# seismometer_energyboard.net
KiCad netlist of a schematic drawn in EAGLE
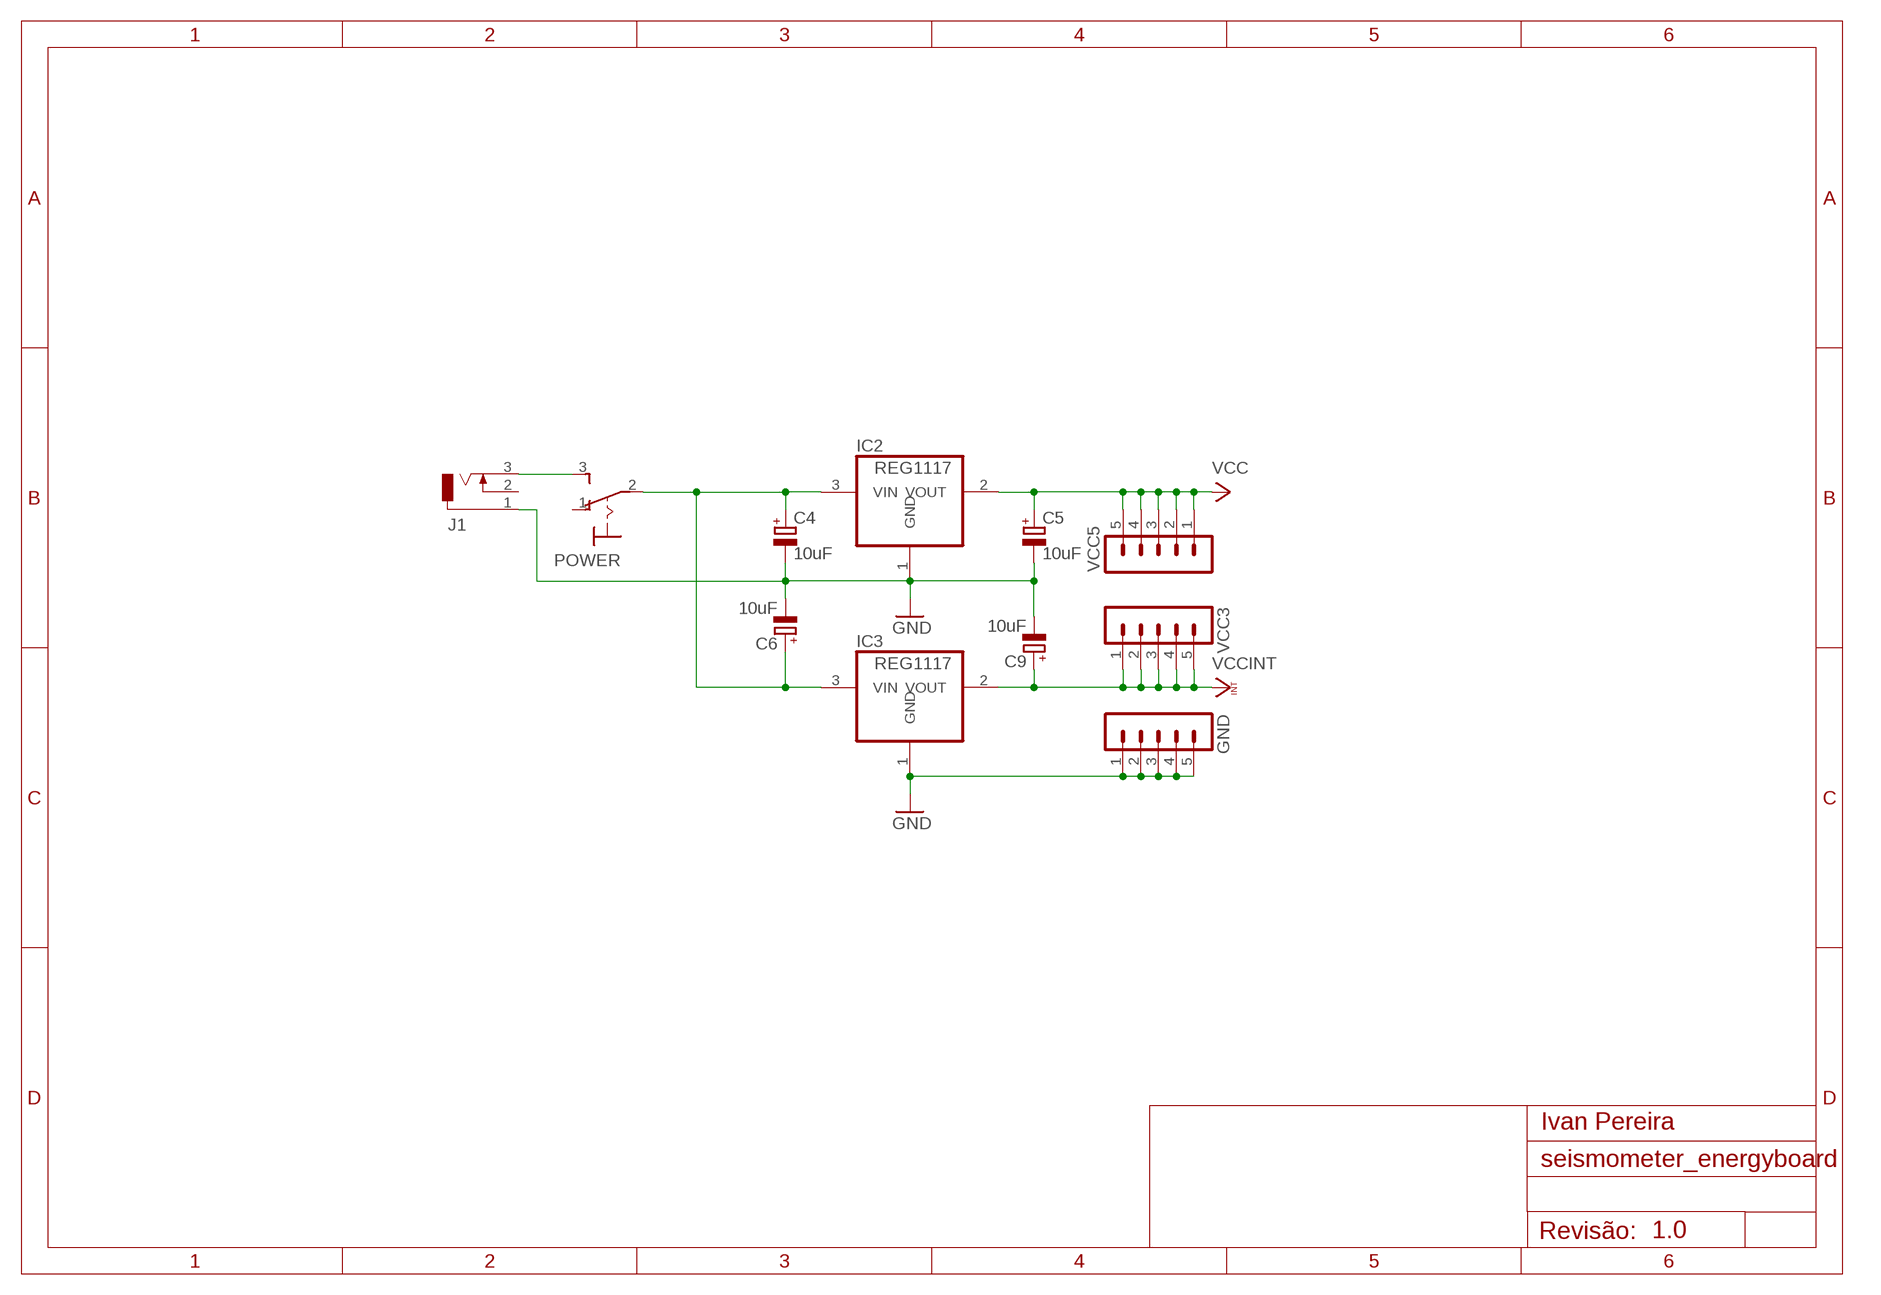
[diagram p0: schematic, sheet 1]

(export (version "E")
  (design (tool "Eeschema 10.0.6"))
  (components
    (comp (ref "C4")
      (value "10uF")
      (footprint "eagle-import:E2,5-6")
      (libsource (lib "eagle-import") (part "CPOL-EUE2.5-6"))
    )
    (comp (ref "C5")
      (value "10uF")
      (footprint "eagle-import:E2,5-6")
      (libsource (lib "eagle-import") (part "CPOL-EUE2.5-6"))
    )
    (comp (ref "C6")
      (value "10uF")
      (footprint "eagle-import:E2,5-6")
      (libsource (lib "eagle-import") (part "CPOL-EUE2.5-6"))
    )
    (comp (ref "C9")
      (value "10uF")
      (footprint "eagle-import:E2,5-6")
      (libsource (lib "eagle-import") (part "CPOL-EUE2.5-6"))
    )
    (comp (ref "GND")
      (value "MA05-1")
      (footprint "eagle-import:MA05-1")
      (libsource (lib "eagle-import") (part "MA05-1"))
    )
    (comp (ref "IC2")
      (value "REG1117")
      (footprint "eagle-import:SOT223")
      (libsource (lib "eagle-import") (part "REG1117"))
    )
    (comp (ref "IC3")
      (value "REG1117")
      (footprint "eagle-import:SOT223")
      (libsource (lib "eagle-import") (part "REG1117"))
    )
    (comp (ref "J1")
      (value "DCJ0303")
      (footprint "eagle-import:DCJ0303")
      (libsource (lib "eagle-import") (part "DCJ0303"))
    )
    (comp (ref "POWER")
      (value "320-916")
      (footprint "eagle-import:320-916")
      (libsource (lib "eagle-import") (part "320-916"))
    )
    (comp (ref "VCC3")
      (value "MA05-1")
      (footprint "eagle-import:MA05-1")
      (libsource (lib "eagle-import") (part "MA05-1"))
    )
    (comp (ref "VCC5")
      (value "MA05-1")
      (footprint "eagle-import:MA05-1")
      (libsource (lib "eagle-import") (part "MA05-1"))
    )
  )
  (nets
    (net (code "1") (name "GND") (class "Default")
      (node (ref "C4") (pin "-") (pinfunction "-_-") (pintype "passive"))
      (node (ref "C5") (pin "-") (pinfunction "-_-") (pintype "passive"))
      (node (ref "C6") (pin "-") (pinfunction "-_-") (pintype "passive"))
      (node (ref "C9") (pin "-") (pinfunction "-_-") (pintype "passive"))
      (node (ref "GND") (pin "1") (pinfunction "1_1") (pintype "passive"))
      (node (ref "GND") (pin "2") (pinfunction "2_2") (pintype "passive"))
      (node (ref "GND") (pin "3") (pinfunction "3_3") (pintype "passive"))
      (node (ref "GND") (pin "4") (pinfunction "4_4") (pintype "passive"))
      (node (ref "GND") (pin "5") (pinfunction "5_5") (pintype "passive"))
      (node (ref "IC2") (pin "1") (pinfunction "GND_1") (pintype "power_in"))
      (node (ref "IC3") (pin "1") (pinfunction "GND_1") (pintype "power_in"))
      (node (ref "J1") (pin "1") (pinfunction "1_1") (pintype "passive"))
    )
    (net (code "2") (name "Net-(IC2-VIN)") (class "Default")
      (node (ref "C4") (pin "+") (pinfunction "+_+") (pintype "passive"))
      (node (ref "C6") (pin "+") (pinfunction "+_+") (pintype "passive"))
      (node (ref "IC2") (pin "3") (pinfunction "VIN_3") (pintype "input"))
      (node (ref "IC3") (pin "3") (pinfunction "VIN_3") (pintype "input"))
      (node (ref "POWER") (pin "2") (pinfunction "P_2") (pintype "passive"))
    )
    (net (code "3") (name "Net-(POWER-S)") (class "Default")
      (node (ref "J1") (pin "3") (pinfunction "3_3") (pintype "passive"))
      (node (ref "POWER") (pin "3") (pinfunction "S_3") (pintype "passive"))
    )
    (net (code "4") (name "VCC") (class "Default")
      (node (ref "C5") (pin "+") (pinfunction "+_+") (pintype "passive"))
      (node (ref "IC2") (pin "2") (pinfunction "VOUT_2") (pintype "output"))
      (node (ref "VCC5") (pin "1") (pinfunction "1_1") (pintype "passive"))
      (node (ref "VCC5") (pin "2") (pinfunction "2_2") (pintype "passive"))
      (node (ref "VCC5") (pin "3") (pinfunction "3_3") (pintype "passive"))
      (node (ref "VCC5") (pin "4") (pinfunction "4_4") (pintype "passive"))
      (node (ref "VCC5") (pin "5") (pinfunction "5_5") (pintype "passive"))
    )
    (net (code "5") (name "VCCINT") (class "Default")
      (node (ref "C9") (pin "+") (pinfunction "+_+") (pintype "passive"))
      (node (ref "IC3") (pin "2") (pinfunction "VOUT_2") (pintype "output"))
      (node (ref "VCC3") (pin "1") (pinfunction "1_1") (pintype "passive"))
      (node (ref "VCC3") (pin "2") (pinfunction "2_2") (pintype "passive"))
      (node (ref "VCC3") (pin "3") (pinfunction "3_3") (pintype "passive"))
      (node (ref "VCC3") (pin "4") (pinfunction "4_4") (pintype "passive"))
      (node (ref "VCC3") (pin "5") (pinfunction "5_5") (pintype "passive"))
    )
    (net (code "6") (name "unconnected-(J1-Pad2)") (class "Default")
      (node (ref "J1") (pin "2") (pinfunction "2_2") (pintype "passive"))
    )
    (net (code "7") (name "unconnected-(POWER-O-Pad1)") (class "Default")
      (node (ref "POWER") (pin "1") (pinfunction "O_1") (pintype "passive"))
    )
  )
)
